# PA107_Schematic.net
KiCad netlist of a schematic drawn in Altium Designer
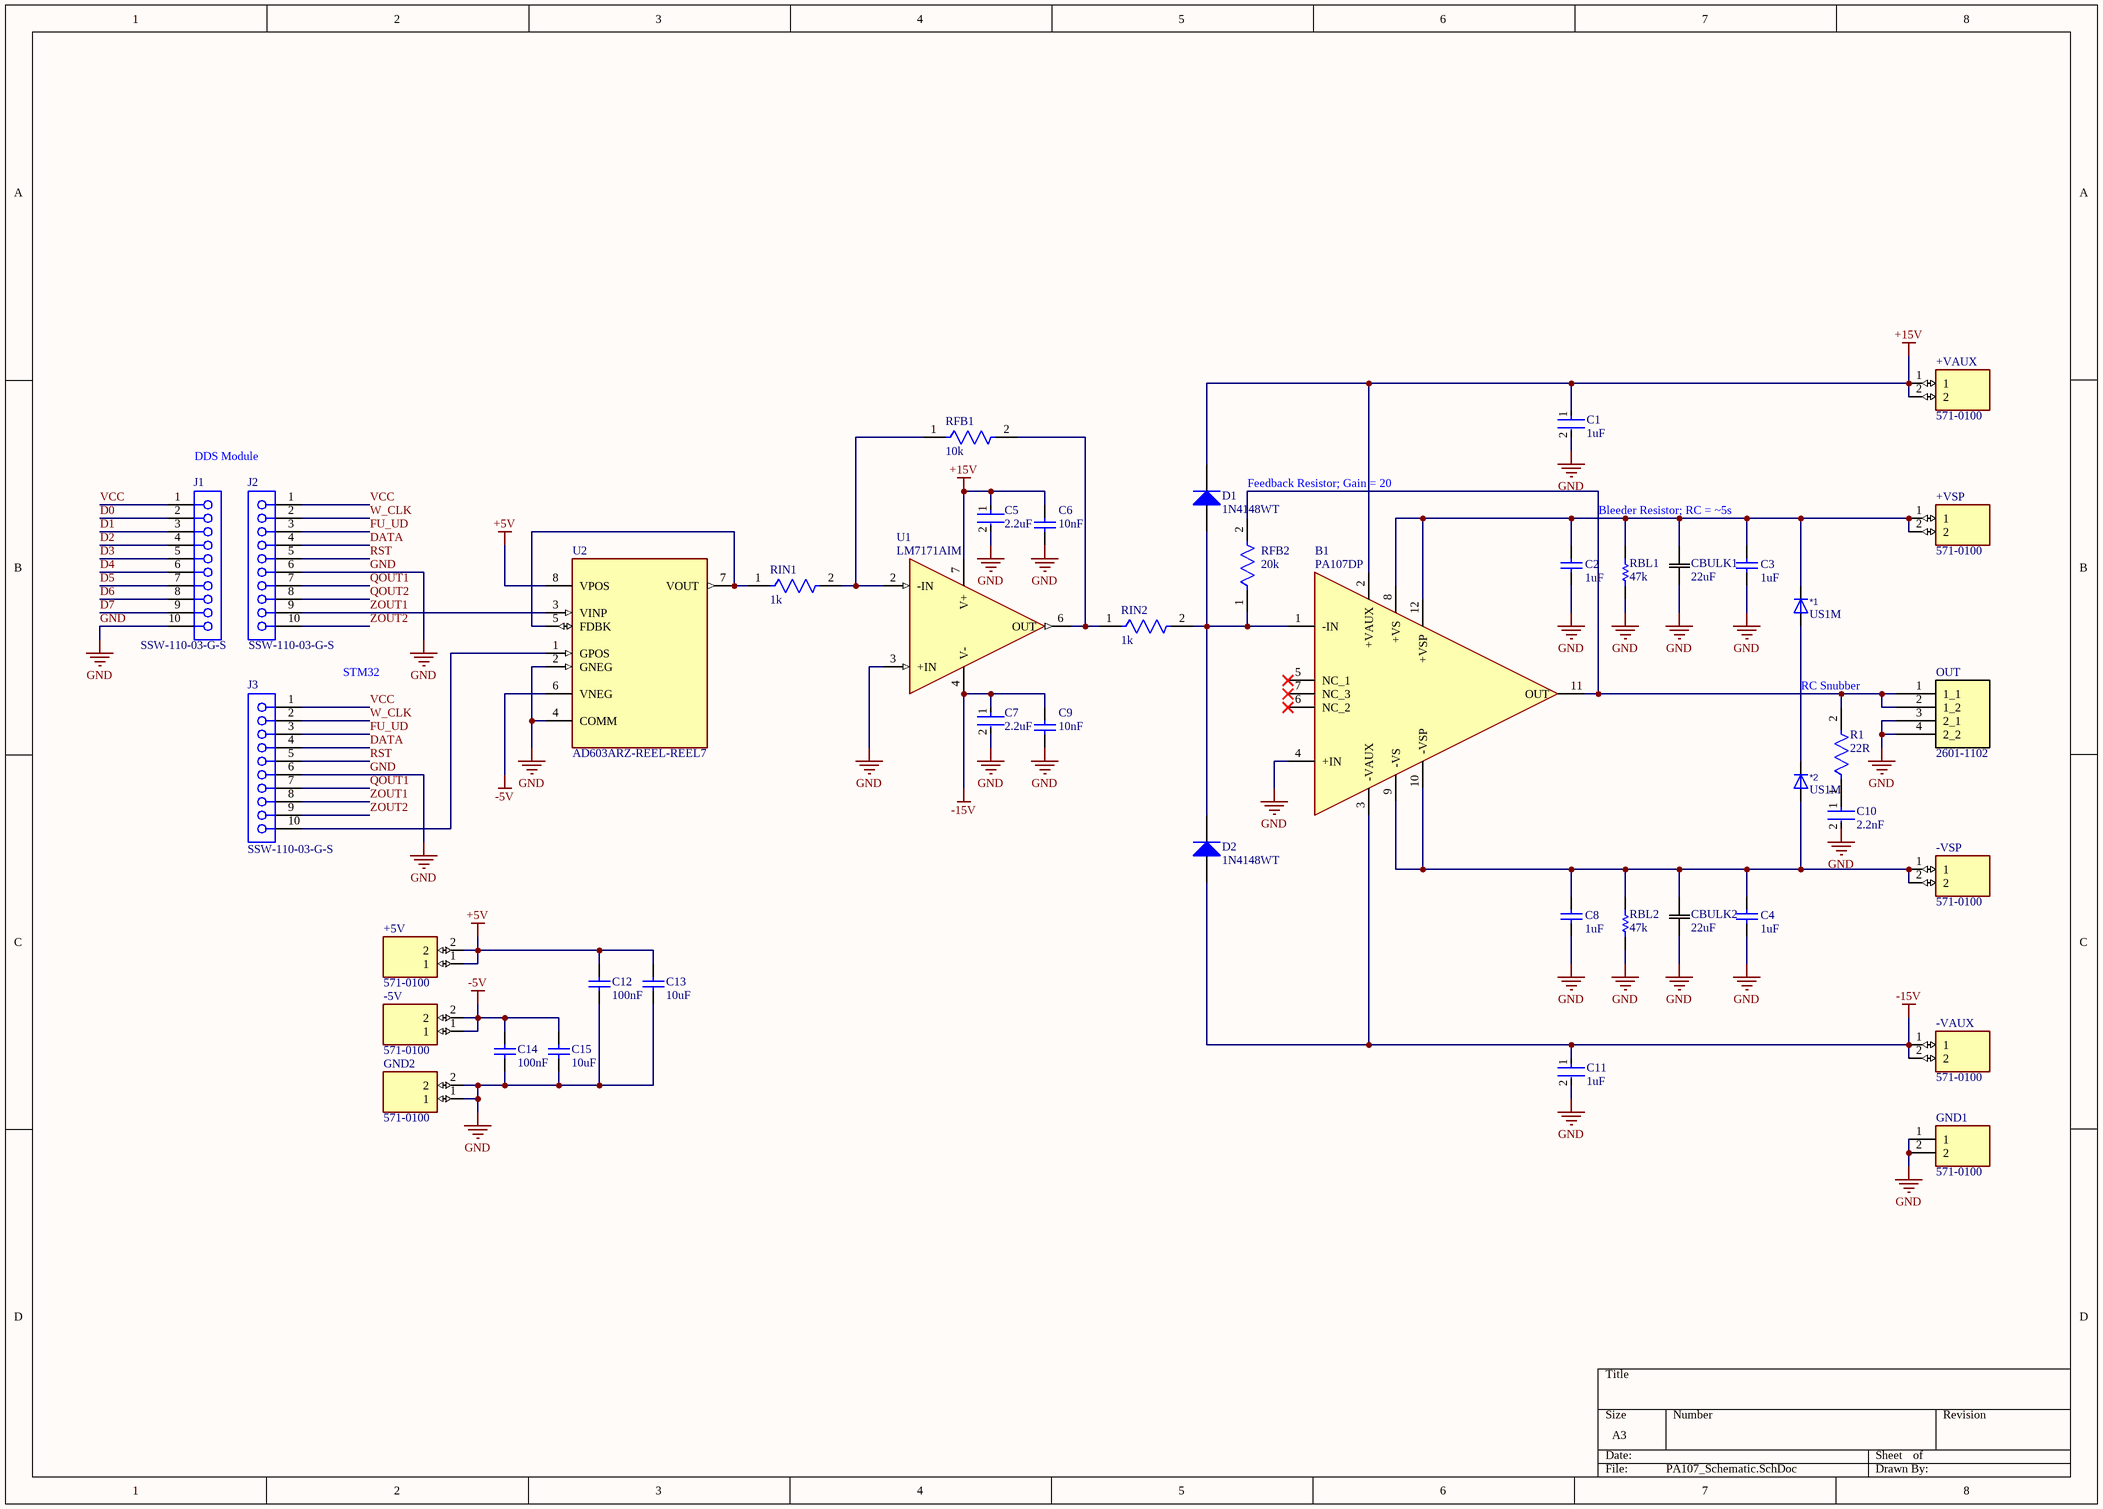
[diagram p0: PA107_Schematic.SchDoc]

(export (version "E")
  (design (tool "Eeschema 10.0.6"))
  (components
    (comp (ref "*1")
      (value "US1M")
      (footprint "DO-214AC_SMA")
      (description "Diode 1000 V 1A Surface Mount DO-214AC (SMA)")
      (libsource (lib "Formula Electric at Berkeley") (part "Diode"))
    )
    (comp (ref "*2")
      (value "US1M")
      (footprint "DO-214AC_SMA")
      (description "Diode 1000 V 1A Surface Mount DO-214AC (SMA)")
      (libsource (lib "Formula Electric at Berkeley") (part "Diode"))
    )
    (comp (ref "+5V")
      (value "571-0100")
      (footprint "571-0100")
      (description "Connector Receptacle, Female Sockets Board Edge, Through Hole, Right Angle Black I-Trac")
      (fields (field (name "MF") "Deltron"))
      (libsource (lib "Formula Electric at Berkeley") (part "571-0100"))
    )
    (comp (ref "+VAUX")
      (value "571-0100")
      (footprint "571-0100")
      (description "Connector Receptacle, Female Sockets Board Edge, Through Hole, Right Angle Black I-Trac")
      (fields (field (name "MF") "Deltron"))
      (libsource (lib "") (part "571-0100_1"))
    )
    (comp (ref "+VSP")
      (value "571-0100")
      (footprint "571-0100")
      (description "Connector Receptacle, Female Sockets Board Edge, Through Hole, Right Angle Black I-Trac")
      (fields (field (name "MF") "Deltron"))
      (libsource (lib "") (part "571-0100_1"))
    )
    (comp (ref "-5V")
      (value "571-0100")
      (footprint "571-0100")
      (description "Connector Receptacle, Female Sockets Board Edge, Through Hole, Right Angle Black I-Trac")
      (fields (field (name "MF") "Deltron"))
      (libsource (lib "Formula Electric at Berkeley") (part "571-0100"))
    )
    (comp (ref "-VAUX")
      (value "571-0100")
      (footprint "571-0100")
      (description "Connector Receptacle, Female Sockets Board Edge, Through Hole, Right Angle Black I-Trac")
      (fields (field (name "MF") "Deltron"))
      (libsource (lib "") (part "571-0100_1"))
    )
    (comp (ref "-VSP")
      (value "571-0100")
      (footprint "571-0100")
      (description "Connector Receptacle, Female Sockets Board Edge, Through Hole, Right Angle Black I-Trac")
      (fields (field (name "MF") "Deltron"))
      (libsource (lib "") (part "571-0100_1"))
    )
    (comp (ref "B1")
      (value "PA107DP")
      (footprint "PA107DP")
      (description "PA107")
      (fields (field (name "MOUSER PART NUMBER") "137-PA107DP"))
      (libsource (lib "Advanced PCB Engineering (APE)") (part "PA107DP"))
    )
    (comp (ref "C1")
      (value "1uF")
      (footprint "FP-CC0805-0_85-MFG")
      (description "CAP CER 1UF 25V X7R 0805")
      (fields (field (name "MANUFACTURER PART NUMBER") "CC0805KKX7R8BB105") (field (name "TOLERANCE") "0.1"))
      (libsource (lib "Altium Content Vault") (part "11868f565c42a9108669ba33697ecf6"))
    )
    (comp (ref "C2")
      (value "1uF")
      (footprint "CAPC4532X279N")
      (description "1 ÂµF Â±10% 200V Ceramic Capacitor X7R 1812 (4532 Metric)")
      (fields (field (name "MF") "AVX") (field (name "MP") "18122C105KAT2A"))
      (libsource (lib "Formula Electric at Berkeley") (part "CAP-NP-2"))
    )
    (comp (ref "C3")
      (value "1uF")
      (footprint "CAPC4532X279N")
      (description "1 ÂµF Â±10% 200V Ceramic Capacitor X7R 1812 (4532 Metric)")
      (fields (field (name "MF") "AVX") (field (name "MP") "18122C105KAT2A"))
      (libsource (lib "Formula Electric at Berkeley") (part "CAP-NP-2"))
    )
    (comp (ref "C4")
      (value "1uF")
      (footprint "CAPC4532X279N")
      (description "1 ÂµF Â±10% 200V Ceramic Capacitor X7R 1812 (4532 Metric)")
      (fields (field (name "MF") "AVX") (field (name "MP") "18122C105KAT2A"))
      (libsource (lib "Formula Electric at Berkeley") (part "CAP-NP-2"))
    )
    (comp (ref "C5")
      (value "2.2uF")
      (footprint "FP-CC0805-0_85-MFG")
      (description "CAP CER 2.2UF 50V X7R 0805")
      (fields
        (field (name "OCTOPART") "https://octopart.com/cc0805kkx7r9bb225-yageo-51849248")
        (field (name "TOLERANCE") "0.1")
      )
      (libsource (lib "Altium Content Vault") (part "11868f565c42a9108669ba33697ecf6"))
    )
    (comp (ref "C6")
      (value "10nF")
      (footprint "CAPC2013X145X48LL20T23")
      (description "10000 pF ±10% 50V Ceramic Capacitor X7R 0805 (2012 Metric)")
      (fields (field (name "MANUFACTURER") "Vitramon") (field (name "PART NUMBER") "VJ0805Y103KXAMP"))
      (libsource (lib "Altium Content Vault") (part "CAP"))
    )
    (comp (ref "C7")
      (value "2.2uF")
      (footprint "FP-CC0805-0_85-MFG")
      (description "CAP CER 2.2UF 50V X7R 0805")
      (fields
        (field (name "OCTOPART") "https://octopart.com/cc0805kkx7r9bb225-yageo-51849248")
        (field (name "TOLERANCE") "0.1")
      )
      (libsource (lib "Altium Content Vault") (part "11868f565c42a9108669ba33697ecf6"))
    )
    (comp (ref "C8")
      (value "1uF")
      (footprint "CAPC4532X279N")
      (description "1 ÂµF Â±10% 200V Ceramic Capacitor X7R 1812 (4532 Metric)")
      (fields (field (name "MF") "AVX") (field (name "MP") "18122C105KAT2A"))
      (libsource (lib "Formula Electric at Berkeley") (part "CAP-NP-2"))
    )
    (comp (ref "C9")
      (value "10nF")
      (footprint "CAPC2013X145X48LL20T23")
      (description "10000 pF ±10% 50V Ceramic Capacitor X7R 0805 (2012 Metric)")
      (fields (field (name "MANUFACTURER") "Vitramon") (field (name "PART NUMBER") "VJ0805Y103KXAMP"))
      (libsource (lib "Altium Content Vault") (part "CAP"))
    )
    (comp (ref "C10")
      (value "2.2nF")
      (footprint "FP-HV1812-IPC_A")
      (description "HV1812Y222KXHATHV Multilayer Ceramic Capacitor, 2200 pF, 3000 V, ± 10%, X7R, 1812 [4532 Metric]")
      (fields (field (name "TOLERANCE") "10%"))
      (libsource (lib "Altium Content Vault") (part "11868f565c42a9108669ba33697ecf6"))
    )
    (comp (ref "C11")
      (value "1uF")
      (footprint "FP-CC0805-0_85-MFG")
      (description "CAP CER 1UF 25V X7R 0805")
      (fields (field (name "MANUFACTURER PART NUMBER") "CC0805KKX7R8BB105") (field (name "TOLERANCE") "0.1"))
      (libsource (lib "Altium Content Vault") (part "11868f565c42a9108669ba33697ecf6"))
    )
    (comp (ref "C12")
      (value "100nF")
      (footprint "CAPC2013X145X48LL20T23")
      (fields (field (name "PART NUMBER") "VJ0805Y104MXAMT") (field (name "MANUFACTURER") "Vitramon"))
      (libsource (lib "Altium Content Vault") (part "CAP"))
    )
    (comp (ref "C13")
      (value "10uF")
      (footprint "CAPC2013X140X50ML20T25")
      (fields
        (field (name "MANUFACTURER") "AVX Interconnect / Elco")
        (field (name "PART NUMBER") "0805ZC106KAT2A")
      )
      (libsource (lib "Altium Content Vault") (part "CAP"))
    )
    (comp (ref "C14")
      (value "100nF")
      (footprint "CAPC2013X145X48LL20T23")
      (fields (field (name "PART NUMBER") "VJ0805Y104MXAMT") (field (name "MANUFACTURER") "Vitramon"))
      (libsource (lib "Altium Content Vault") (part "CAP"))
    )
    (comp (ref "C15")
      (value "10uF")
      (footprint "CAPC2013X140X50ML20T25")
      (fields
        (field (name "MANUFACTURER") "AVX Interconnect / Elco")
        (field (name "PART NUMBER") "0805ZC106KAT2A")
      )
      (libsource (lib "Altium Content Vault") (part "CAP"))
    )
    (comp (ref "CBULK1")
      (value "22uF")
      (footprint "CAP_BX_10x16_RUB")
      (description "No Description Available")
      (fields
        (field (name "MANUFACTURER_PART_NUMBER") "250BXC22MEFCT810X16")
        (field (name "COPYRIGHT") "Copyright (C) 2026 Ultra Librarian. All rights reserved.")
      )
      (libsource (lib "Formula Electric at Berkeley") (part "250BXC22MEFCT810X16"))
    )
    (comp (ref "CBULK2")
      (value "22uF")
      (footprint "CAP_BX_10x16_RUB")
      (description "No Description Available")
      (fields
        (field (name "MANUFACTURER_PART_NUMBER") "250BXC22MEFCT810X16")
        (field (name "COPYRIGHT") "Copyright (C) 2026 Ultra Librarian. All rights reserved.")
      )
      (libsource (lib "Formula Electric at Berkeley") (part "250BXC22MEFCT810X16"))
    )
    (comp (ref "D1")
      (value "1N4148WT")
      (footprint "FAIR-SOD-523F-2_V")
      (description "High Conductance Fast Switching Diode, 75 V, -55 to 150 degC, 2-Pin SOD523F, RoHS")
      (fields (field (name "MANUFACTURER") "Fairchild Semiconductor"))
      (libsource (lib "Altium Content Vault") (part "FAIR-D_K1A2-2"))
    )
    (comp (ref "D2")
      (value "1N4148WT")
      (footprint "FAIR-SOD-523F-2_V")
      (description "High Conductance Fast Switching Diode, 75 V, -55 to 150 degC, 2-Pin SOD523F, RoHS")
      (fields (field (name "MANUFACTURER") "Fairchild Semiconductor"))
      (libsource (lib "Altium Content Vault") (part "FAIR-D_K1A2-2"))
    )
    (comp (ref "GND1")
      (value "571-0100")
      (footprint "5710100")
      (description "Test Sockets SINGLE PCB SOCK BLK")
      (fields (field (name "MOUSER PART NUMBER") "164-6218"))
      (libsource (lib "Advanced PCB Engineering (APE)") (part "571-0100"))
    )
    (comp (ref "GND2")
      (value "571-0100")
      (footprint "571-0100")
      (description "Connector Receptacle, Female Sockets Board Edge, Through Hole, Right Angle Black I-Trac")
      (fields (field (name "MF") "Deltron"))
      (libsource (lib "Formula Electric at Berkeley") (part "571-0100"))
    )
    (comp (ref "J1")
      (value "SSW-110-03-G-S")
      (footprint "SMTC-SSW-110-03-X-S")
      (description "SQ Post Socket, Through-hole, Vertical, -55 to 125 degC, 2.54 mm Pitch, 10-Pin, Female, RoHS")
      (fields (field (name "MANUFACTURER") "Samtec"))
      (libsource (lib "Altium Content Vault") (part "SMTC-SSW-110-03-X-S"))
    )
    (comp (ref "J2")
      (value "SSW-110-03-G-S")
      (footprint "SMTC-SSW-110-03-X-S")
      (description "SQ Post Socket, Through-hole, Vertical, -55 to 125 degC, 2.54 mm Pitch, 10-Pin, Female, RoHS")
      (fields (field (name "MANUFACTURER") "Samtec"))
      (libsource (lib "Altium Content Vault") (part "SMTC-SSW-110-03-X-S"))
    )
    (comp (ref "J3")
      (value "SSW-110-03-G-S")
      (footprint "SMTC-SSW-110-03-X-S")
      (description "SQ Post Socket, Through-hole, Vertical, -55 to 125 degC, 2.54 mm Pitch, 10-Pin, Female, RoHS")
      (fields (field (name "MANUFACTURER") "Samtec"))
      (libsource (lib "Altium Content Vault") (part "SMTC-SSW-110-03-X-S"))
    )
    (comp (ref "OUT")
      (value "2601-1102")
      (footprint "CONN2_2601-1102_WAG")
      (description "Description")
      (fields (field (name "COPYRIGHT") "Copyright (C) 2026 Ultra Librarian. All rights reserved."))
      (libsource (lib "Formula Electric at Berkeley") (part "2601-1102"))
    )
    (comp (ref "R1")
      (value "22R")
      (footprint "FP-CRGP2512-IPC_C")
      (description "CRGP2512 22Ω 2W ±100ppm/°C 1% 500V")
      (fields (field (name "MANUFACTURER PART NUMBER") "CRGP2512F22R") (field (name "MANUFACTURER") "TE"))
      (libsource (lib "Altium Content Vault") (part "1029c3af85768c4190bb7ad29bc67b5"))
    )
    (comp (ref "RBL1")
      (value "47k")
      (footprint "RESC1210(3225)_L")
      (description "47K 0.5W 5% 1210 (3225 Metric)  SMD")
      (fields (field (name "POWER") "0.5 W") (field (name "TOLERANCE") "5 %"))
      (libsource (lib "Altium Content Vault") (part "RES"))
    )
    (comp (ref "RBL2")
      (value "47k")
      (footprint "RESC1210(3225)_L")
      (description "47K 0.5W 5% 1210 (3225 Metric)  SMD")
      (fields (field (name "POWER") "0.5 W") (field (name "TOLERANCE") "5 %"))
      (libsource (lib "Altium Content Vault") (part "RES"))
    )
    (comp (ref "RFB1")
      (value "10k")
      (footprint "FP-SR0805-MFG")
      (description "SR0805 10KΩ 0.5W 1.00%")
      (fields (field (name "MANUFACTURER PART NUMBER") "SR0805FR-4710KL"))
      (libsource (lib "Altium Content Vault") (part "1029c3af85768c4190bb7ad29bc67b5"))
    )
    (comp (ref "RFB2")
      (value "20k")
      (footprint "FP-CRCW0805-HPe3-IPC_A")
      (description "RES Thick Film, 20kΩ, 1%, 0.5W, 100ppm/°C, 0805")
      (fields (field (name "TOLERANCE") "1%"))
      (libsource (lib "Altium Content Vault") (part "1029c3af85768c4190bb7ad29bc67b5"))
    )
    (comp (ref "RIN1")
      (value "1k")
      (footprint "FP-CRCW0805-HPe3-IPC_B")
      (description "RES Thick Film, 1kΩ, 5%, 0.5W, 200ppm/°C, 0805")
      (fields (field (name "TOLERANCE") "5%"))
      (libsource (lib "Altium Content Vault") (part "1029c3af85768c4190bb7ad29bc67b5"))
    )
    (comp (ref "RIN2")
      (value "1k")
      (footprint "FP-CRCW0805-HPe3-IPC_B")
      (description "RES Thick Film, 1kΩ, 5%, 0.5W, 200ppm/°C, 0805")
      (fields (field (name "TOLERANCE") "5%"))
      (libsource (lib "Altium Content Vault") (part "1029c3af85768c4190bb7ad29bc67b5"))
    )
    (comp (ref "U1")
      (value "LM7171AIM")
      (footprint "SOIC127P599X175-8N")
      (description "Very High Speed, High Output Current, Voltage Feedback Amplifier")
      (fields (field (name "MF") "Texas Instruments") (field (name "MP") "LM7171AIMX/NOPB"))
      (libsource (lib "Formula Electric at Berkeley") (part "LM7171AIM"))
    )
    (comp (ref "U2")
      (value "AD603ARZ-REEL-REEL7")
      (footprint "SOIC127P600X175-8N")
      (description "Low Noise, 90 MHz Variable Gain Amplifier")
      (fields (field (name "MF") "Analog Devices") (field (name "MP") "AD603ARZ-REEL7"))
      (libsource (lib "Formula Electric at Berkeley") (part "AD603ARZ-REEL-REEL7"))
    )
  )
  (nets
    (net (code "1") (name "+5V") (class "Default")
      (node (ref "+5V") (pin "1") (pinfunction "1_1") (pintype "bidirectional"))
      (node (ref "+5V") (pin "2") (pinfunction "2_2") (pintype "bidirectional"))
      (node (ref "C12") (pin "2") (pinfunction "2_2") (pintype "passive"))
      (node (ref "C13") (pin "2") (pinfunction "2_2") (pintype "passive"))
      (node (ref "U2") (pin "8") (pinfunction "VPOS_8") (pintype "power_in"))
    )
    (net (code "2") (name "+15V") (class "Default")
      (node (ref "+VAUX") (pin "1") (pinfunction "1_1") (pintype "bidirectional"))
      (node (ref "+VAUX") (pin "2") (pinfunction "2_2") (pintype "bidirectional"))
      (node (ref "B1") (pin "2") (pinfunction "+VAUX_2") (pintype "passive"))
      (node (ref "C1") (pin "1") (pinfunction "1_1") (pintype "passive"))
      (node (ref "C5") (pin "1") (pinfunction "1_1") (pintype "passive"))
      (node (ref "C6") (pin "2") (pinfunction "2_2") (pintype "passive"))
      (node (ref "D1") (pin "1") (pinfunction "K_1") (pintype "passive"))
      (node (ref "U1") (pin "7") (pinfunction "V+_7") (pintype "power_in"))
    )
    (net (code "3") (name "-5V") (class "Default")
      (node (ref "-5V") (pin "1") (pinfunction "1_1") (pintype "bidirectional"))
      (node (ref "-5V") (pin "2") (pinfunction "2_2") (pintype "bidirectional"))
      (node (ref "C14") (pin "2") (pinfunction "2_2") (pintype "passive"))
      (node (ref "C15") (pin "2") (pinfunction "2_2") (pintype "passive"))
      (node (ref "U2") (pin "6") (pinfunction "VNEG_6") (pintype "power_in"))
    )
    (net (code "4") (name "-15V") (class "Default")
      (node (ref "-VAUX") (pin "1") (pinfunction "1_1") (pintype "bidirectional"))
      (node (ref "-VAUX") (pin "2") (pinfunction "2_2") (pintype "bidirectional"))
      (node (ref "B1") (pin "3") (pinfunction "-VAUX_3") (pintype "passive"))
      (node (ref "C11") (pin "1") (pinfunction "1_1") (pintype "passive"))
      (node (ref "C7") (pin "1") (pinfunction "1_1") (pintype "passive"))
      (node (ref "C9") (pin "2") (pinfunction "2_2") (pintype "passive"))
      (node (ref "D2") (pin "2") (pinfunction "A_2") (pintype "passive"))
      (node (ref "U1") (pin "4") (pinfunction "V-_4") (pintype "power_in"))
    )
    (net (code "5") (name "/D0") (class "Default")
      (node (ref "J1") (pin "2") (pinfunction "2_2") (pintype "passive"))
    )
    (net (code "6") (name "/D1") (class "Default")
      (node (ref "J1") (pin "3") (pinfunction "3_3") (pintype "passive"))
    )
    (net (code "7") (name "/D2") (class "Default")
      (node (ref "J1") (pin "4") (pinfunction "4_4") (pintype "passive"))
    )
    (net (code "8") (name "/D3") (class "Default")
      (node (ref "J1") (pin "5") (pinfunction "5_5") (pintype "passive"))
    )
    (net (code "9") (name "/D4") (class "Default")
      (node (ref "J1") (pin "6") (pinfunction "6_6") (pintype "passive"))
    )
    (net (code "10") (name "/D5") (class "Default")
      (node (ref "J1") (pin "7") (pinfunction "7_7") (pintype "passive"))
    )
    (net (code "11") (name "/D6") (class "Default")
      (node (ref "J1") (pin "8") (pinfunction "8_8") (pintype "passive"))
    )
    (net (code "12") (name "/D7") (class "Default")
      (node (ref "J1") (pin "9") (pinfunction "9_9") (pintype "passive"))
    )
    (net (code "13") (name "/DATA") (class "Default")
      (node (ref "J2") (pin "4") (pinfunction "4_4") (pintype "passive"))
      (node (ref "J3") (pin "4") (pinfunction "4_4") (pintype "passive"))
    )
    (net (code "14") (name "/FU_UD") (class "Default")
      (node (ref "J2") (pin "3") (pinfunction "3_3") (pintype "passive"))
      (node (ref "J3") (pin "3") (pinfunction "3_3") (pintype "passive"))
    )
    (net (code "15") (name "/QOUT1") (class "Default")
      (node (ref "J2") (pin "7") (pinfunction "7_7") (pintype "passive"))
      (node (ref "J3") (pin "7") (pinfunction "7_7") (pintype "passive"))
    )
    (net (code "16") (name "/QOUT2") (class "Default")
      (node (ref "J2") (pin "8") (pinfunction "8_8") (pintype "passive"))
    )
    (net (code "17") (name "/RST") (class "Default")
      (node (ref "J2") (pin "5") (pinfunction "5_5") (pintype "passive"))
      (node (ref "J3") (pin "5") (pinfunction "5_5") (pintype "passive"))
    )
    (net (code "18") (name "/VCC") (class "Default")
      (node (ref "J1") (pin "1") (pinfunction "1_1") (pintype "passive"))
      (node (ref "J2") (pin "1") (pinfunction "1_1") (pintype "passive"))
      (node (ref "J3") (pin "1") (pinfunction "1_1") (pintype "passive"))
    )
    (net (code "19") (name "/W_CLK") (class "Default")
      (node (ref "J2") (pin "2") (pinfunction "2_2") (pintype "passive"))
      (node (ref "J3") (pin "2") (pinfunction "2_2") (pintype "passive"))
    )
    (net (code "20") (name "/ZOUT1") (class "Default")
      (node (ref "J2") (pin "9") (pinfunction "9_9") (pintype "passive"))
      (node (ref "J3") (pin "8") (pinfunction "8_8") (pintype "passive"))
      (node (ref "U2") (pin "3") (pinfunction "VINP_3") (pintype "input"))
    )
    (net (code "21") (name "/ZOUT2") (class "Default")
      (node (ref "J2") (pin "10") (pinfunction "10_10") (pintype "passive"))
      (node (ref "J3") (pin "9") (pinfunction "9_9") (pintype "passive"))
    )
    (net (code "22") (name "GND") (class "Default")
      (node (ref "B1") (pin "4") (pinfunction "+IN_4") (pintype "passive"))
      (node (ref "C1") (pin "2") (pinfunction "2_2") (pintype "passive"))
      (node (ref "C10") (pin "2") (pinfunction "2_2") (pintype "passive"))
      (node (ref "C11") (pin "2") (pinfunction "2_2") (pintype "passive"))
      (node (ref "C12") (pin "1") (pinfunction "1_1") (pintype "passive"))
      (node (ref "C13") (pin "1") (pinfunction "1_1") (pintype "passive"))
      (node (ref "C14") (pin "1") (pinfunction "1_1") (pintype "passive"))
      (node (ref "C15") (pin "1") (pinfunction "1_1") (pintype "passive"))
      (node (ref "C2") (pin "1") (pinfunction "1_1") (pintype "passive"))
      (node (ref "C3") (pin "1") (pinfunction "1_1") (pintype "passive"))
      (node (ref "C4") (pin "1") (pinfunction "1_1") (pintype "passive"))
      (node (ref "C5") (pin "2") (pinfunction "2_2") (pintype "passive"))
      (node (ref "C6") (pin "1") (pinfunction "1_1") (pintype "passive"))
      (node (ref "C7") (pin "2") (pinfunction "2_2") (pintype "passive"))
      (node (ref "C8") (pin "1") (pinfunction "1_1") (pintype "passive"))
      (node (ref "C9") (pin "1") (pinfunction "1_1") (pintype "passive"))
      (node (ref "CBULK1") (pin "1") (pinfunction "1_1") (pintype "passive"))
      (node (ref "CBULK2") (pin "1") (pinfunction "1_1") (pintype "passive"))
      (node (ref "GND1") (pin "1") (pinfunction "1_1") (pintype "passive"))
      (node (ref "GND1") (pin "2") (pinfunction "2_2") (pintype "passive"))
      (node (ref "GND2") (pin "1") (pinfunction "1_1") (pintype "bidirectional"))
      (node (ref "GND2") (pin "2") (pinfunction "2_2") (pintype "bidirectional"))
      (node (ref "J1") (pin "10") (pinfunction "10_10") (pintype "passive"))
      (node (ref "J2") (pin "6") (pinfunction "6_6") (pintype "passive"))
      (node (ref "J3") (pin "6") (pinfunction "6_6") (pintype "passive"))
      (node (ref "OUT") (pin "3") (pinfunction "2_1_3") (pintype "passive"))
      (node (ref "OUT") (pin "4") (pinfunction "2_2_4") (pintype "passive"))
      (node (ref "RBL1") (pin "1") (pinfunction "1_1") (pintype "passive"))
      (node (ref "RBL2") (pin "1") (pinfunction "1_1") (pintype "passive"))
      (node (ref "U1") (pin "3") (pinfunction "+IN_3") (pintype "input"))
      (node (ref "U2") (pin "2") (pinfunction "GNEG_2") (pintype "input"))
      (node (ref "U2") (pin "4") (pinfunction "COMM_4") (pintype "passive"))
    )
    (net (code "23") (name "Net-(*1-A)") (class "Default")
      (node (ref "*1") (pin "2") (pinfunction "A_2") (pintype "passive"))
      (node (ref "*2") (pin "1") (pinfunction "K_1") (pintype "passive"))
    )
    (net (code "24") (name "Net-(*1-K)") (class "Default")
      (node (ref "*1") (pin "1") (pinfunction "K_1") (pintype "passive"))
      (node (ref "+VSP") (pin "1") (pinfunction "1_1") (pintype "bidirectional"))
      (node (ref "+VSP") (pin "2") (pinfunction "2_2") (pintype "bidirectional"))
      (node (ref "B1") (pin "12") (pinfunction "+VSP_12") (pintype "passive"))
      (node (ref "B1") (pin "8") (pinfunction "+VS_8") (pintype "passive"))
      (node (ref "C2") (pin "2") (pinfunction "2_2") (pintype "passive"))
      (node (ref "C3") (pin "2") (pinfunction "2_2") (pintype "passive"))
      (node (ref "CBULK1") (pin "2") (pinfunction "2_2") (pintype "passive"))
      (node (ref "RBL1") (pin "2") (pinfunction "2_2") (pintype "passive"))
    )
    (net (code "25") (name "Net-(*2-A)") (class "Default")
      (node (ref "*2") (pin "2") (pinfunction "A_2") (pintype "passive"))
      (node (ref "-VSP") (pin "1") (pinfunction "1_1") (pintype "bidirectional"))
      (node (ref "-VSP") (pin "2") (pinfunction "2_2") (pintype "bidirectional"))
      (node (ref "B1") (pin "10") (pinfunction "-VSP_10") (pintype "passive"))
      (node (ref "B1") (pin "9") (pinfunction "-VS_9") (pintype "passive"))
      (node (ref "C4") (pin "2") (pinfunction "2_2") (pintype "passive"))
      (node (ref "C8") (pin "2") (pinfunction "2_2") (pintype "passive"))
      (node (ref "CBULK2") (pin "2") (pinfunction "2_2") (pintype "passive"))
      (node (ref "RBL2") (pin "2") (pinfunction "2_2") (pintype "passive"))
    )
    (net (code "26") (name "Net-(B1--IN)") (class "Default")
      (node (ref "B1") (pin "1") (pinfunction "-IN_1") (pintype "passive"))
      (node (ref "D1") (pin "2") (pinfunction "A_2") (pintype "passive"))
      (node (ref "D2") (pin "1") (pinfunction "K_1") (pintype "passive"))
      (node (ref "RFB2") (pin "1") (pinfunction "1_1") (pintype "passive"))
      (node (ref "RIN2") (pin "2") (pinfunction "2_2") (pintype "passive"))
    )
    (net (code "27") (name "Net-(B1-OUT)") (class "Default")
      (node (ref "B1") (pin "11") (pinfunction "OUT_11") (pintype "passive"))
      (node (ref "OUT") (pin "1") (pinfunction "1_1_1") (pintype "passive"))
      (node (ref "OUT") (pin "2") (pinfunction "1_2_2") (pintype "passive"))
      (node (ref "R1") (pin "2") (pinfunction "2_2") (pintype "passive"))
      (node (ref "RFB2") (pin "2") (pinfunction "2_2") (pintype "passive"))
    )
    (net (code "28") (name "Net-(C10-Pad1)") (class "Default")
      (node (ref "C10") (pin "1") (pinfunction "1_1") (pintype "passive"))
      (node (ref "R1") (pin "1") (pinfunction "1_1") (pintype "passive"))
    )
    (net (code "29") (name "Net-(U1--IN)") (class "Default")
      (node (ref "RFB1") (pin "1") (pinfunction "1_1") (pintype "passive"))
      (node (ref "RIN1") (pin "2") (pinfunction "2_2") (pintype "passive"))
      (node (ref "U1") (pin "2") (pinfunction "-IN_2") (pintype "input"))
    )
    (net (code "30") (name "Net-(U1-OUT)") (class "Default")
      (node (ref "RFB1") (pin "2") (pinfunction "2_2") (pintype "passive"))
      (node (ref "RIN2") (pin "1") (pinfunction "1_1") (pintype "passive"))
      (node (ref "U1") (pin "6") (pinfunction "OUT_6") (pintype "output"))
    )
    (net (code "31") (name "Net-(U2-FDBK)") (class "Default")
      (node (ref "RIN1") (pin "1") (pinfunction "1_1") (pintype "passive"))
      (node (ref "U2") (pin "5") (pinfunction "FDBK_5") (pintype "bidirectional"))
      (node (ref "U2") (pin "7") (pinfunction "VOUT_7") (pintype "output"))
    )
    (net (code "32") (name "Net-(U2-GPOS)") (class "Default")
      (node (ref "J3") (pin "10") (pinfunction "10_10") (pintype "passive"))
      (node (ref "U2") (pin "1") (pinfunction "GPOS_1") (pintype "input"))
    )
    (net (code "33") (name "unconnected-(B1-NC_1-Pad5)") (class "Default")
      (node (ref "B1") (pin "5") (pinfunction "NC_1_5") (pintype "passive+no_connect"))
    )
    (net (code "34") (name "unconnected-(B1-NC_2-Pad6)") (class "Default")
      (node (ref "B1") (pin "6") (pinfunction "NC_2_6") (pintype "passive+no_connect"))
    )
    (net (code "35") (name "unconnected-(B1-NC_3-Pad7)") (class "Default")
      (node (ref "B1") (pin "7") (pinfunction "NC_3_7") (pintype "passive+no_connect"))
    )
  )
)
